# SCH_Doly_CE_Charger_2212.net
KiCad netlist of a schematic drawn in EasyEDA
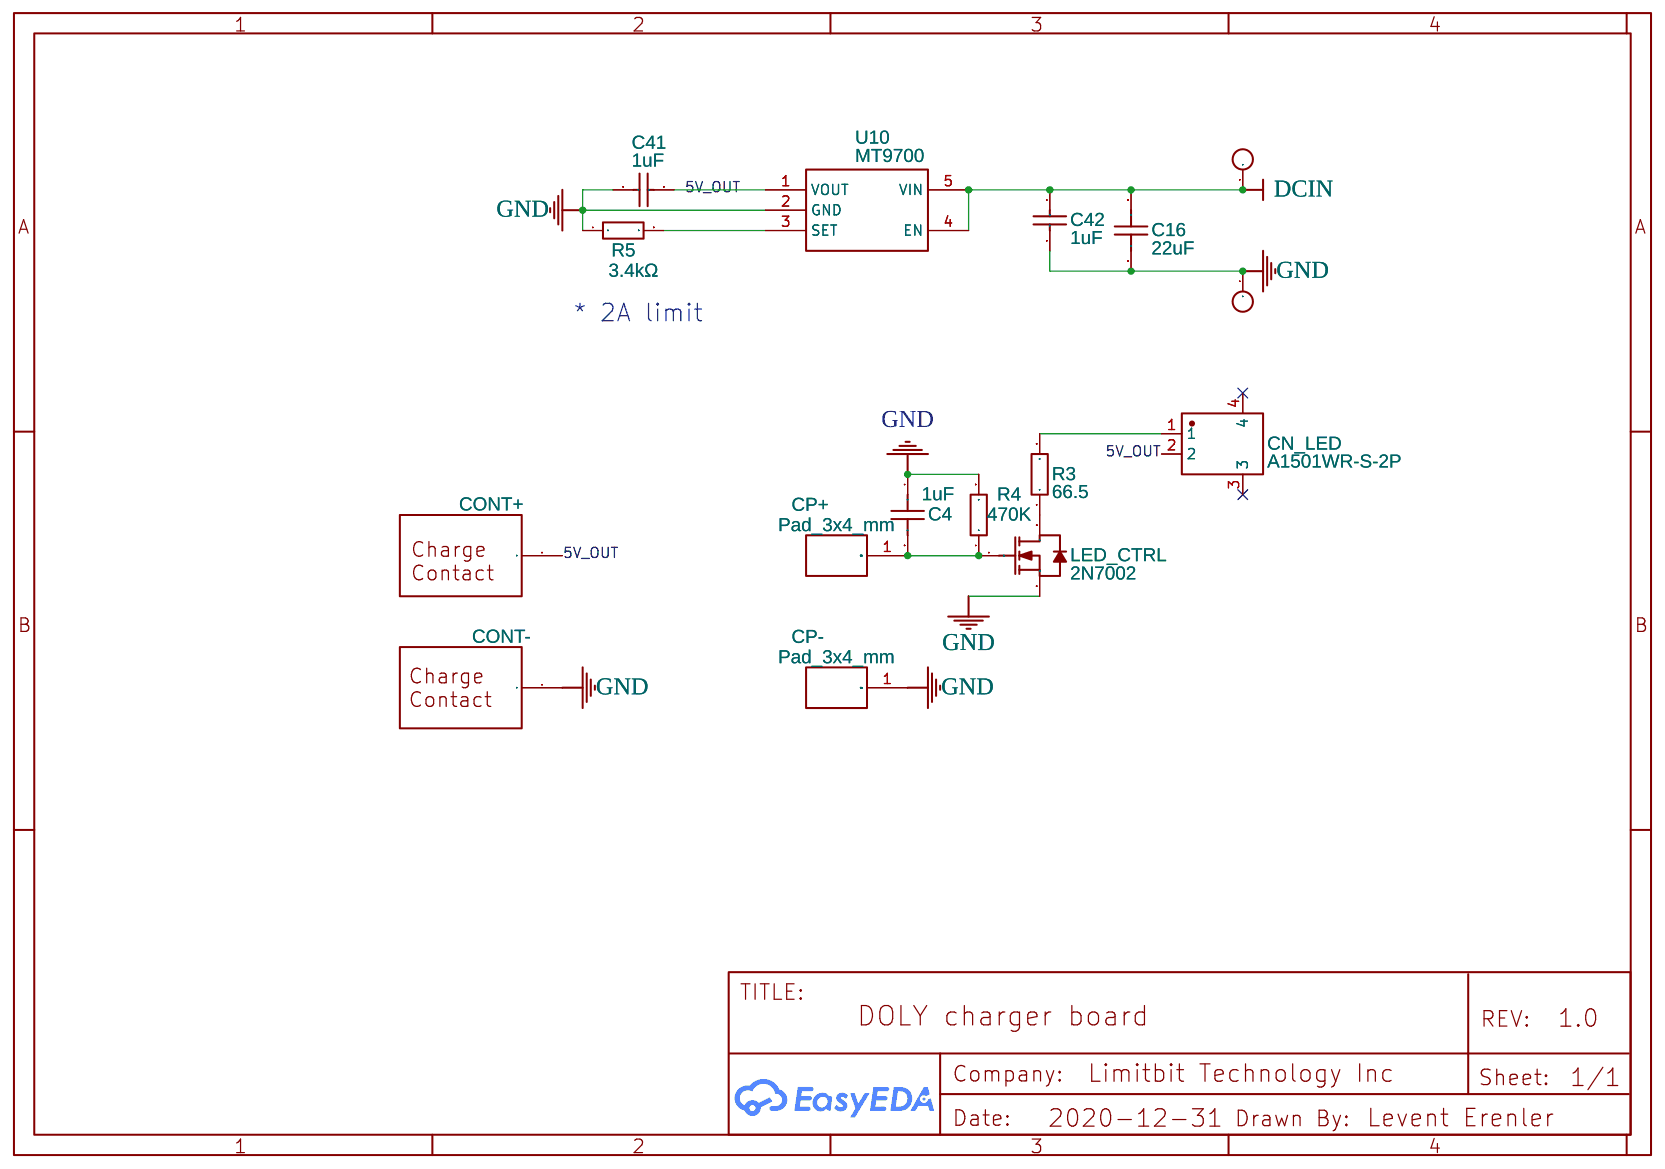
[diagram p0: schematic sheet]

(export (version "E")
  (design (tool "Eeschema 10.0.6"))
  (components
    (comp (ref "+5V") (value "TP_1.5MM") (libsource (lib "") (part "TP_1.5MM_1")))
    (comp (ref "-") (value "TP_1.5MM") (libsource (lib "") (part "TP_1.5MM")))
    (comp (ref "C4")
      (value "1uF")
      (fields (field (name "Manufacturer Part") "CL10A105KP8NNNC") (field (name "Manufacturer") "SAMSUNG"))
      (libsource (lib "") (part "CL10A106KP8NNNC"))
    )
    (comp (ref "C16")
      (value "22uF")
      (fields (field (name "Manufacturer Part") "GRM188R61A226ME15D") (field (name "Manufacturer") "MuRata"))
      (libsource (lib "") (part "GRM188R61A226ME15D"))
    )
    (comp (ref "C41")
      (value "1uF")
      (fields (field (name "Manufacturer Part") "CL10A105KA8NNNC") (field (name "Manufacturer") "SAMSUNG"))
      (libsource (lib "") (part "CL10A105KA8NNNC"))
    )
    (comp (ref "C42")
      (value "1uF")
      (fields (field (name "Manufacturer Part") "CL10A105KA8NNNC") (field (name "Manufacturer") "SAMSUNG"))
      (libsource (lib "") (part "CL10A105KA8NNNC_1"))
    )
    (comp (ref "CN_LED")
      (value "A1501WR-S-2P")
      (fields (field (name "Manufacturer") "Changjiang Connectors"))
      (libsource (lib "") (part "A1501WR-S-2P"))
    )
    (comp (ref "CONT+") (value "DockChargeContact") (libsource (lib "") (part "DockChargeContact")))
    (comp (ref "CONT-") (value "DockChargeContact") (libsource (lib "") (part "DockChargeContact_1")))
    (comp (ref "CP+") (value "Pad_3x4_mm") (libsource (lib "") (part "Pad_3x4_mm")))
    (comp (ref "CP-") (value "Pad_3x4_mm") (libsource (lib "") (part "Pad_3x4_mm_1")))
    (comp (ref "LED_CTRL")
      (value "2N7002")
      (fields (field (name "Manufacturer Part") "2N7002(Silk screen12W)") (field (name "Manufacturer") "SK"))
      (libsource (lib "") (part "Unknown_495_-295"))
    )
    (comp (ref "R3")
      (value "66.5")
      (fields (field (name "Manufacturer Part") "0603WAF665JT5E") (field (name "Manufacturer") "UniOhm"))
      (libsource (lib "") (part "0603WAF665JT5E"))
    )
    (comp (ref "R4")
      (value "470K")
      (fields (field (name "Manufacturer Part") "0603WAF4703T5E") (field (name "Manufacturer") "UniOhm"))
      (libsource (lib "") (part "0603WAF4703T5E"))
    )
    (comp (ref "R5")
      (value "3.4kΩ")
      (fields
        (field (name "Manufacturer Part") "0603WAF3401T5E")
        (field (name "Manufacturer") "UNI-ROYAL(厚声)")
      )
      (libsource (lib "") (part "0603WAF3401T5E"))
    )
    (comp (ref "U10")
      (value "MT9700")
      (fields (field (name "Manufacturer") "AEROSEMI"))
      (libsource (lib "") (part "MT9700"))
    )
  )
  (nets
    (net (code "1") (name "/5V_OUT") (class "Default")
      (node (ref "C41") (pin "1") (pinfunction "1_1") (pintype "input"))
      (node (ref "CN_LED") (pin "2") (pinfunction "2_2") (pintype "unspecified"))
      (node (ref "CONT+") (pin "1") (pinfunction "1_1") (pintype "unspecified"))
      (node (ref "U10") (pin "1") (pinfunction "VOUT_1") (pintype "unspecified"))
    )
    (net (code "2") (name "DCIN") (class "Default")
      (node (ref "+5V") (pin "1") (pinfunction "1_1") (pintype "unspecified"))
      (node (ref "C16") (pin "2") (pinfunction "2_2") (pintype "unspecified"))
      (node (ref "C42") (pin "1") (pinfunction "1_1") (pintype "input"))
      (node (ref "U10") (pin "4") (pinfunction "EN_4") (pintype "unspecified"))
      (node (ref "U10") (pin "5") (pinfunction "VIN_5") (pintype "unspecified"))
    )
    (net (code "3") (name "GND") (class "Default")
      (node (ref "-") (pin "1") (pinfunction "1_1") (pintype "unspecified"))
      (node (ref "C16") (pin "1") (pinfunction "1_1") (pintype "unspecified"))
      (node (ref "C4") (pin "1") (pinfunction "1_1") (pintype "unspecified"))
      (node (ref "C41") (pin "2") (pinfunction "2_2") (pintype "input"))
      (node (ref "C42") (pin "2") (pinfunction "2_2") (pintype "input"))
      (node (ref "CONT-") (pin "1") (pinfunction "1_1") (pintype "unspecified"))
      (node (ref "CP-") (pin "1") (pinfunction "CN_3x4mm_1") (pintype "unspecified"))
      (node (ref "LED_CTRL") (pin "2") (pinfunction "S_2") (pintype "unspecified"))
      (node (ref "R4") (pin "2") (pinfunction "2_2") (pintype "input"))
      (node (ref "R5") (pin "1") (pinfunction "1_1") (pintype "input"))
      (node (ref "U10") (pin "2") (pinfunction "GND_2") (pintype "unspecified"))
    )
    (net (code "4") (name "Net-(CN_LED-Pad1)") (class "Default")
      (node (ref "CN_LED") (pin "1") (pinfunction "1_1") (pintype "unspecified"))
      (node (ref "R3") (pin "2") (pinfunction "2_2") (pintype "input"))
    )
    (net (code "5") (name "Net-(CP+-CN_3x4mm)") (class "Default")
      (node (ref "C4") (pin "2") (pinfunction "2_2") (pintype "unspecified"))
      (node (ref "CP+") (pin "1") (pinfunction "CN_3x4mm_1") (pintype "unspecified"))
      (node (ref "LED_CTRL") (pin "1") (pinfunction "G_1") (pintype "unspecified"))
      (node (ref "R4") (pin "1") (pinfunction "1_1") (pintype "input"))
    )
    (net (code "6") (name "Net-(LED_CTRL-D)") (class "Default")
      (node (ref "LED_CTRL") (pin "3") (pinfunction "D_3") (pintype "unspecified"))
      (node (ref "R3") (pin "1") (pinfunction "1_1") (pintype "input"))
    )
    (net (code "7") (name "Net-(U10-SET)") (class "Default")
      (node (ref "R5") (pin "2") (pinfunction "2_2") (pintype "input"))
      (node (ref "U10") (pin "3") (pinfunction "SET_3") (pintype "unspecified"))
    )
    (net (code "8") (name "unconnected-(CN_LED-Pad3)") (class "Default")
      (node (ref "CN_LED") (pin "3") (pinfunction "3_3") (pintype "unspecified+no_connect"))
    )
    (net (code "9") (name "unconnected-(CN_LED-Pad4)") (class "Default")
      (node (ref "CN_LED") (pin "4") (pinfunction "4_4") (pintype "unspecified+no_connect"))
    )
  )
)
